# TMS320F28335_DSP.net
KiCad netlist of a schematic drawn in Altium Designer
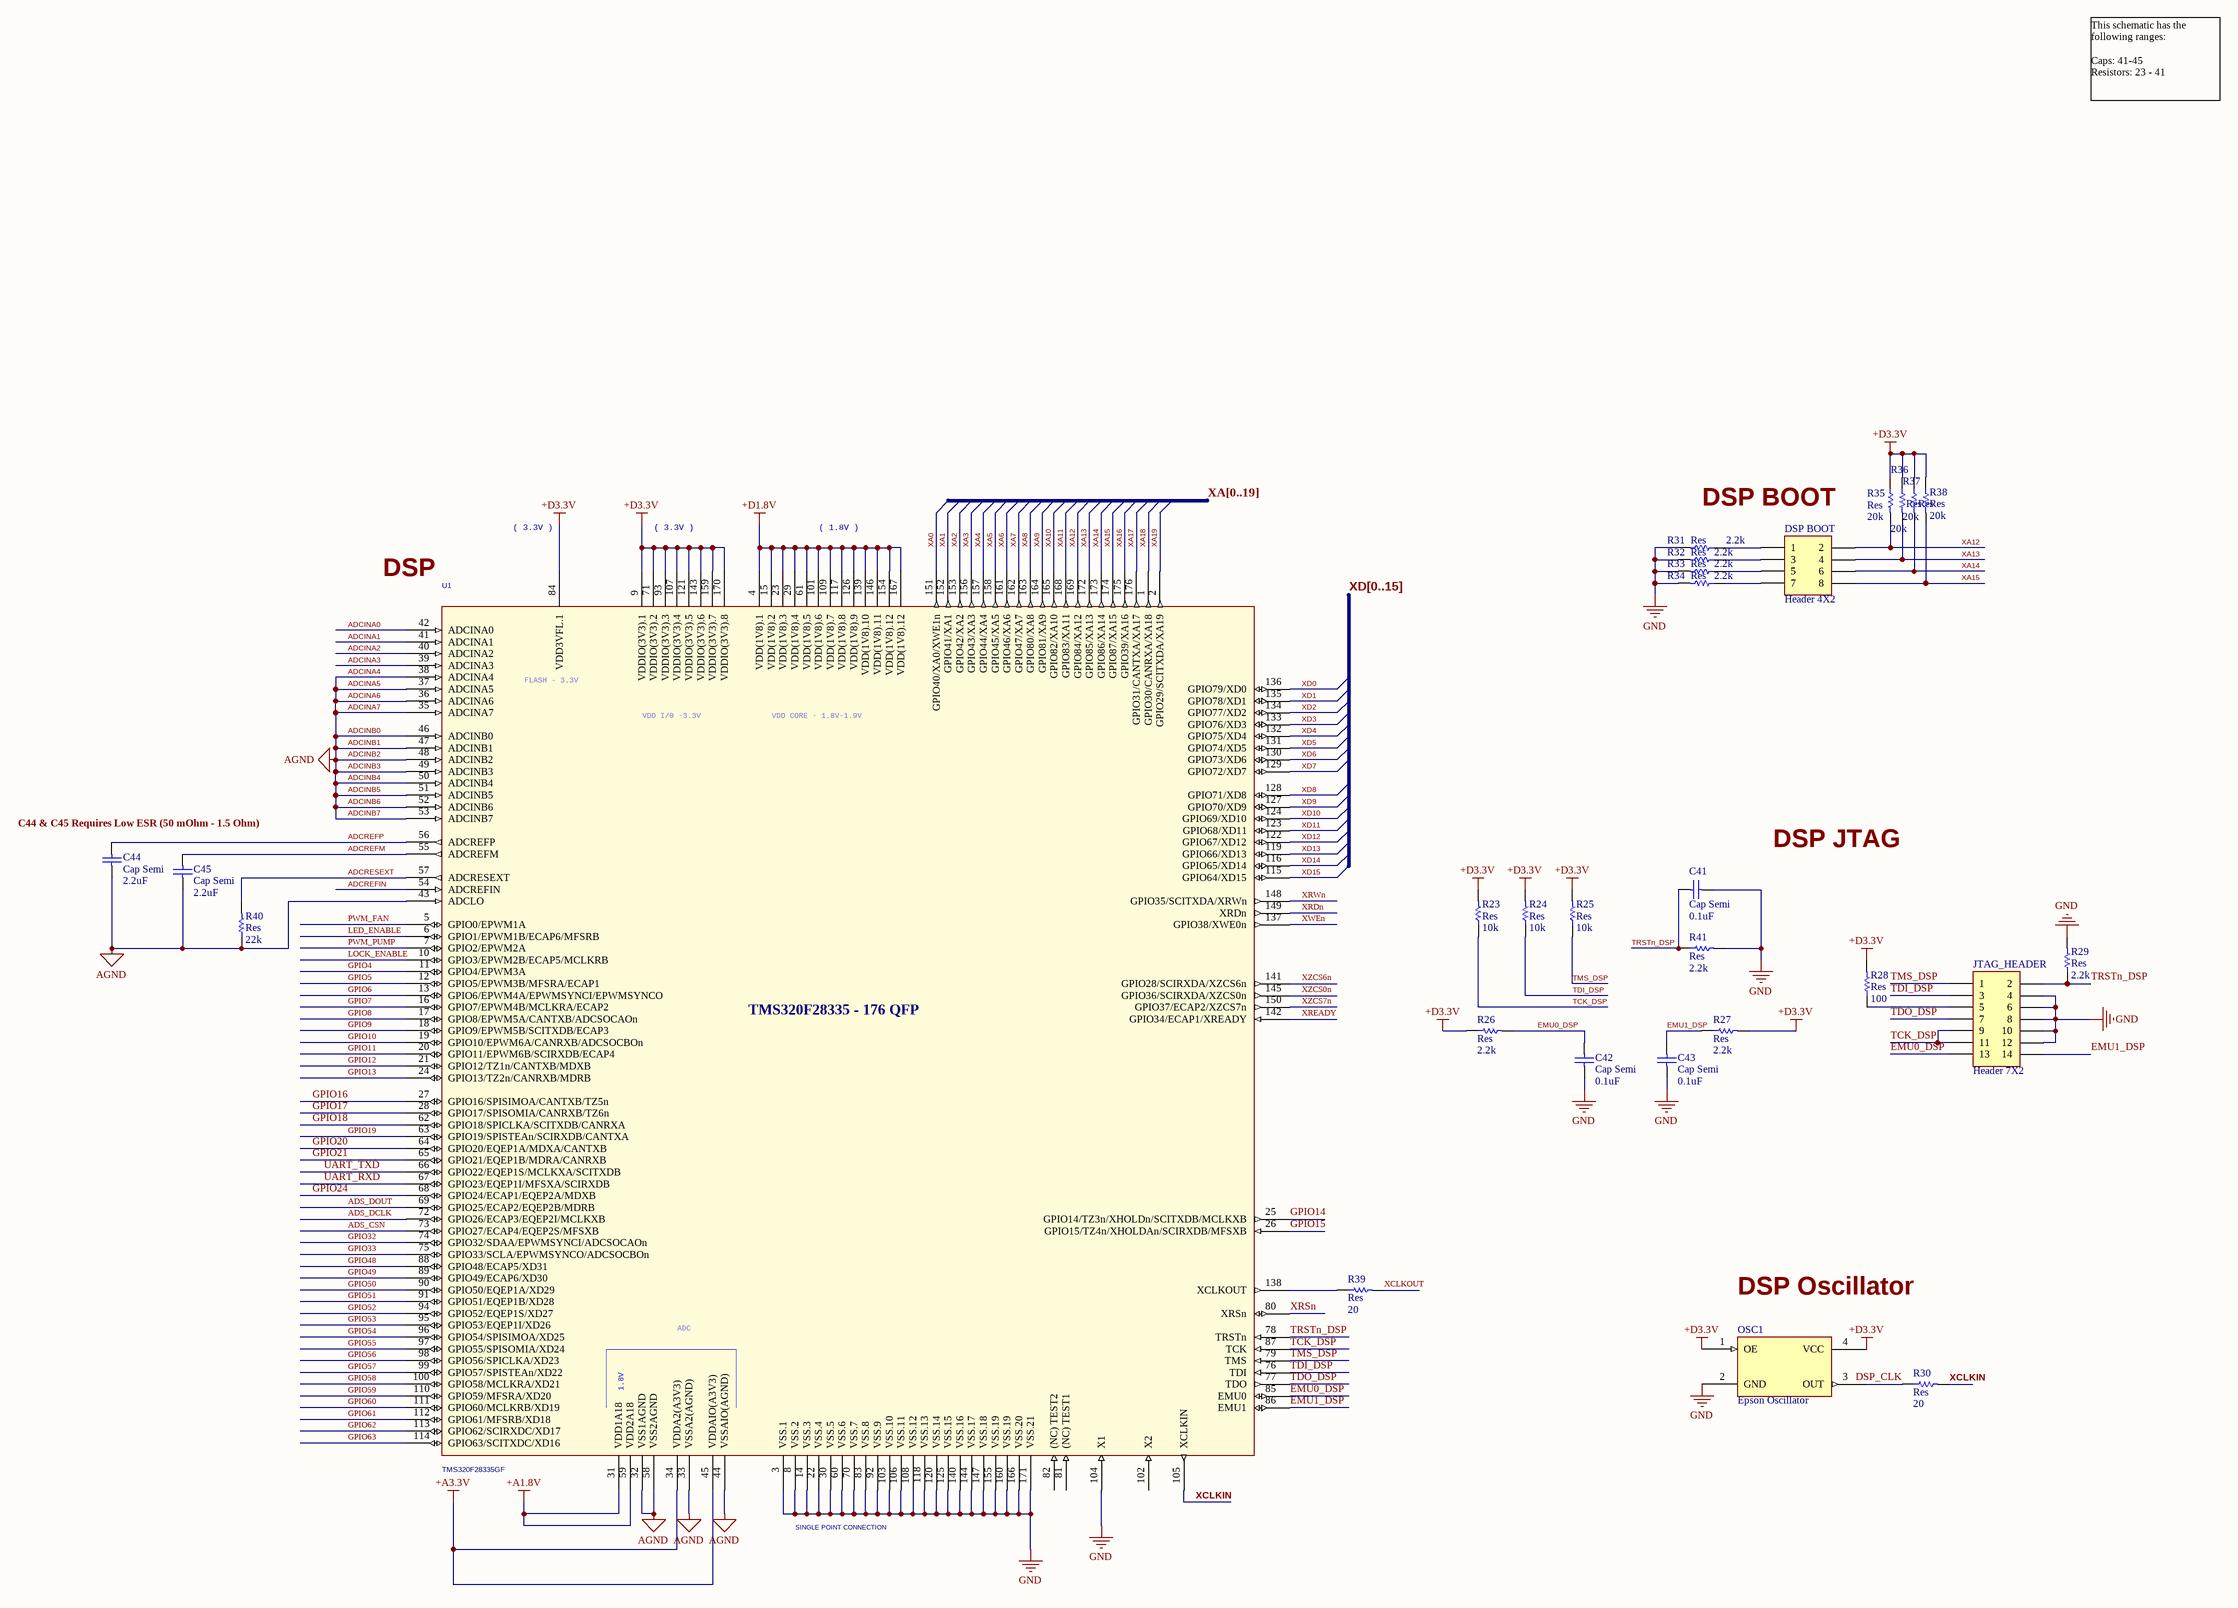
[diagram p0: TMS320F28335_DSP.SchDoc]

(export (version "E")
  (design (tool "Eeschema 10.0.6"))
  (components
    (comp (ref "C41")
      (value "Cap Semi")
      (footprint "0805")
      (description "Capacitor (Semiconductor SIM Model)")
      (fields (field (name "ALTIUM_VALUE") "0.1uF") (field (name "PUBLISHER") "Altium Limited"))
      (libsource (lib "Miscellaneous Devices") (part "Cap Semi"))
    )
    (comp (ref "C42")
      (value "Cap Semi")
      (footprint "0805")
      (description "Capacitor (Semiconductor SIM Model)")
      (fields (field (name "ALTIUM_VALUE") "0.1uF") (field (name "PUBLISHER") "Altium Limited"))
      (libsource (lib "Miscellaneous Devices") (part "Cap Semi"))
    )
    (comp (ref "C43")
      (value "Cap Semi")
      (footprint "0805")
      (description "Capacitor (Semiconductor SIM Model)")
      (fields (field (name "ALTIUM_VALUE") "0.1uF") (field (name "PUBLISHER") "Altium Limited"))
      (libsource (lib "Miscellaneous Devices") (part "Cap Semi"))
    )
    (comp (ref "C44")
      (value "Cap Semi")
      (footprint "0805")
      (description "Capacitor (Semiconductor SIM Model)")
      (fields (field (name "ALTIUM_VALUE") "2.2uF") (field (name "PUBLISHER") "Altium Limited"))
      (libsource (lib "Miscellaneous Devices") (part "Cap Semi"))
    )
    (comp (ref "C45")
      (value "Cap Semi")
      (footprint "0805")
      (description "Capacitor (Semiconductor SIM Model)")
      (fields (field (name "ALTIUM_VALUE") "2.2uF") (field (name "PUBLISHER") "Altium Limited"))
      (libsource (lib "Miscellaneous Devices") (part "Cap Semi"))
    )
    (comp (ref "DSP BOOT")
      (value "Header 4X2")
      (footprint "HDR2X4")
      (description "Header, 4-Pin, Dual row")
      (fields (field (name "PUBLISHER") "Altium Limited"))
      (libsource (lib "Miscellaneous Connectors") (part "Header 4X2"))
    )
    (comp (ref "JTAG_HEADER")
      (value "Header 7X2")
      (footprint "HDR2X7")
      (description "Header, 7-Pin, Dual row")
      (fields (field (name "PUBLISHER") "Altium Limited"))
      (libsource (lib "Miscellaneous Connectors") (part "Header 7X2"))
    )
    (comp (ref "OSC1")
      (value "Epson Oscillator")
      (footprint "Oscillator")
      (description "15Mhz Epson Clock")
      (libsource (lib "F28335_DSC_Breakout") (part "Oscillator"))
    )
    (comp (ref "R23")
      (value "Res")
      (footprint "0805")
      (description "Semiconductor Resistor")
      (fields (field (name "ALTIUM_VALUE") "10k") (field (name "PUBLISHER") "Altium Limited"))
      (libsource (lib "F28335_DSC_Breakout") (part "Res Semi"))
    )
    (comp (ref "R24")
      (value "Res")
      (footprint "0805")
      (description "Semiconductor Resistor")
      (fields (field (name "ALTIUM_VALUE") "10k") (field (name "PUBLISHER") "Altium Limited"))
      (libsource (lib "F28335_DSC_Breakout") (part "Res Semi"))
    )
    (comp (ref "R25")
      (value "Res")
      (footprint "0805")
      (description "Semiconductor Resistor")
      (fields (field (name "ALTIUM_VALUE") "10k") (field (name "PUBLISHER") "Altium Limited"))
      (libsource (lib "F28335_DSC_Breakout") (part "Res Semi"))
    )
    (comp (ref "R26")
      (value "Res")
      (footprint "0805")
      (description "Semiconductor Resistor")
      (fields (field (name "ALTIUM_VALUE") "2.2k") (field (name "PUBLISHER") "Altium Limited"))
      (libsource (lib "F28335_DSC_Breakout") (part "Res Semi"))
    )
    (comp (ref "R27")
      (value "Res")
      (footprint "0805")
      (description "Semiconductor Resistor")
      (fields (field (name "ALTIUM_VALUE") "2.2k") (field (name "PUBLISHER") "Altium Limited"))
      (libsource (lib "F28335_DSC_Breakout") (part "Res Semi"))
    )
    (comp (ref "R28")
      (value "Res")
      (footprint "0805")
      (description "Semiconductor Resistor")
      (fields (field (name "ALTIUM_VALUE") "100") (field (name "PUBLISHER") "Altium Limited"))
      (libsource (lib "F28335_DSC_Breakout") (part "Res Semi"))
    )
    (comp (ref "R29")
      (value "Res")
      (footprint "0805")
      (description "Semiconductor Resistor")
      (fields (field (name "ALTIUM_VALUE") "2.2k") (field (name "PUBLISHER") "Altium Limited"))
      (libsource (lib "F28335_DSC_Breakout") (part "Res Semi"))
    )
    (comp (ref "R30")
      (value "Res")
      (footprint "0805")
      (description "Semiconductor Resistor")
      (fields (field (name "ALTIUM_VALUE") "20") (field (name "PUBLISHER") "Altium Limited"))
      (libsource (lib "F28335_DSC_Breakout") (part "Res Semi"))
    )
    (comp (ref "R31")
      (value "Res")
      (footprint "0805")
      (description "Semiconductor Resistor")
      (fields (field (name "ALTIUM_VALUE") "2.2k") (field (name "PUBLISHER") "Altium Limited"))
      (libsource (lib "F28335_DSC_Breakout") (part "Res Semi"))
    )
    (comp (ref "R32")
      (value "Res")
      (footprint "0805")
      (description "Semiconductor Resistor")
      (fields (field (name "ALTIUM_VALUE") "2.2k") (field (name "PUBLISHER") "Altium Limited"))
      (libsource (lib "F28335_DSC_Breakout") (part "Res Semi"))
    )
    (comp (ref "R33")
      (value "Res")
      (footprint "0805")
      (description "Semiconductor Resistor")
      (fields (field (name "ALTIUM_VALUE") "2.2k") (field (name "PUBLISHER") "Altium Limited"))
      (libsource (lib "F28335_DSC_Breakout") (part "Res Semi"))
    )
    (comp (ref "R34")
      (value "Res")
      (footprint "0805")
      (description "Semiconductor Resistor")
      (fields (field (name "ALTIUM_VALUE") "2.2k") (field (name "PUBLISHER") "Altium Limited"))
      (libsource (lib "F28335_DSC_Breakout") (part "Res Semi"))
    )
    (comp (ref "R35")
      (value "Res")
      (footprint "0805")
      (description "Semiconductor Resistor")
      (fields (field (name "ALTIUM_VALUE") "20k") (field (name "PUBLISHER") "Altium Limited"))
      (libsource (lib "F28335_DSC_Breakout") (part "Res Semi"))
    )
    (comp (ref "R36")
      (value "Res")
      (footprint "0805")
      (description "Semiconductor Resistor")
      (fields (field (name "ALTIUM_VALUE") "20k") (field (name "PUBLISHER") "Altium Limited"))
      (libsource (lib "F28335_DSC_Breakout") (part "Res Semi"))
    )
    (comp (ref "R37")
      (value "Res")
      (footprint "0805")
      (description "Semiconductor Resistor")
      (fields (field (name "ALTIUM_VALUE") "20k") (field (name "PUBLISHER") "Altium Limited"))
      (libsource (lib "F28335_DSC_Breakout") (part "Res Semi"))
    )
    (comp (ref "R38")
      (value "Res")
      (footprint "0805")
      (description "Semiconductor Resistor")
      (fields (field (name "ALTIUM_VALUE") "20k") (field (name "PUBLISHER") "Altium Limited"))
      (libsource (lib "F28335_DSC_Breakout") (part "Res Semi"))
    )
    (comp (ref "R39")
      (value "Res")
      (footprint "0805")
      (description "Semiconductor Resistor")
      (fields (field (name "ALTIUM_VALUE") "20") (field (name "PUBLISHER") "Altium Limited"))
      (libsource (lib "F28335_DSC_Breakout") (part "Res Semi"))
    )
    (comp (ref "R40")
      (value "Res")
      (footprint "0805")
      (description "Semiconductor Resistor")
      (fields (field (name "ALTIUM_VALUE") "22k") (field (name "PUBLISHER") "Altium Limited"))
      (libsource (lib "F28335_DSC_Breakout") (part "Res Semi"))
    )
    (comp (ref "R41")
      (value "Res")
      (footprint "0805")
      (description "Semiconductor Resistor")
      (fields (field (name "ALTIUM_VALUE") "2.2k") (field (name "PUBLISHER") "Altium Limited"))
      (libsource (lib "F28335_DSC_Breakout") (part "Res Semi"))
    )
    (comp (ref "U1")
      (value "TMS320F28335GF")
      (footprint "QFP176")
      (description "Texas Instruments F28335")
      (libsource (lib "addl") (part "TMS320F283XXPGF_23"))
    )
  )
  (nets
    (net (code "1") (name "+A1.8V") (class "Default")
      (node (ref "U1") (pin "31") (pinfunction "VDD1A18_31") (pintype "power_in"))
      (node (ref "U1") (pin "59") (pinfunction "VDD2A18_59") (pintype "power_in"))
    )
    (net (code "2") (name "+A3.3V") (class "Default")
      (node (ref "U1") (pin "34") (pinfunction "VDDA2(A3V3)_34") (pintype "power_in"))
      (node (ref "U1") (pin "45") (pinfunction "VDDAIO(A3V3)_45") (pintype "power_in"))
    )
    (net (code "3") (name "+D1.8V") (class "Default")
      (node (ref "U1") (pin "101") (pinfunction "VDD(1V8).6_101") (pintype "power_in"))
      (node (ref "U1") (pin "109") (pinfunction "VDD(1V8).7_109") (pintype "power_in"))
      (node (ref "U1") (pin "117") (pinfunction "VDD(1V8).8_117") (pintype "power_in"))
      (node (ref "U1") (pin "126") (pinfunction "VDD(1V8).9_126") (pintype "power_in"))
      (node (ref "U1") (pin "139") (pinfunction "VDD(1V8).10_139") (pintype "power_in"))
      (node (ref "U1") (pin "146") (pinfunction "VDD(1V8).11_146") (pintype "power_in"))
      (node (ref "U1") (pin "15") (pinfunction "VDD(1V8).2_15") (pintype "power_in"))
      (node (ref "U1") (pin "154") (pinfunction "VDD(1V8).12_154") (pintype "power_in"))
      (node (ref "U1") (pin "167") (pinfunction "VDD(1V8).12_167") (pintype "power_in"))
      (node (ref "U1") (pin "23") (pinfunction "VDD(1V8).3_23") (pintype "power_in"))
      (node (ref "U1") (pin "29") (pinfunction "VDD(1V8).4_29") (pintype "power_in"))
      (node (ref "U1") (pin "4") (pinfunction "VDD(1V8).1_4") (pintype "power_in"))
      (node (ref "U1") (pin "61") (pinfunction "VDD(1V8).5_61") (pintype "power_in"))
    )
    (net (code "4") (name "+D3.3V") (class "Default")
      (node (ref "OSC1") (pin "1") (pinfunction "OE_1") (pintype "input"))
      (node (ref "OSC1") (pin "4") (pinfunction "VCC_4") (pintype "power_in"))
      (node (ref "R23") (pin "2") (pinfunction "2_2") (pintype "passive"))
      (node (ref "R24") (pin "2") (pinfunction "2_2") (pintype "passive"))
      (node (ref "R25") (pin "2") (pinfunction "2_2") (pintype "passive"))
      (node (ref "R26") (pin "1") (pinfunction "1_1") (pintype "passive"))
      (node (ref "R27") (pin "2") (pinfunction "2_2") (pintype "passive"))
      (node (ref "R28") (pin "2") (pinfunction "2_2") (pintype "passive"))
      (node (ref "R35") (pin "1") (pinfunction "1_1") (pintype "passive"))
      (node (ref "R36") (pin "1") (pinfunction "1_1") (pintype "passive"))
      (node (ref "R37") (pin "1") (pinfunction "1_1") (pintype "passive"))
      (node (ref "R38") (pin "1") (pinfunction "1_1") (pintype "passive"))
      (node (ref "U1") (pin "107") (pinfunction "VDDIO(3V3).4_107") (pintype "power_in"))
      (node (ref "U1") (pin "121") (pinfunction "VDDIO(3V3).5_121") (pintype "power_in"))
      (node (ref "U1") (pin "143") (pinfunction "VDDIO(3V3).6_143") (pintype "power_in"))
      (node (ref "U1") (pin "159") (pinfunction "VDDIO(3V3).7_159") (pintype "power_in"))
      (node (ref "U1") (pin "170") (pinfunction "VDDIO(3V3).8_170") (pintype "power_in"))
      (node (ref "U1") (pin "71") (pinfunction "VDDIO(3V3).2_71") (pintype "power_in"))
      (node (ref "U1") (pin "84") (pinfunction "VDD3VFL.1_84") (pintype "power_in"))
      (node (ref "U1") (pin "9") (pinfunction "VDDIO(3V3).1_9") (pintype "power_in"))
      (node (ref "U1") (pin "93") (pinfunction "VDDIO(3V3).3_93") (pintype "power_in"))
    )
    (net (code "5") (name "/ADCINA0") (class "Default")
      (node (ref "U1") (pin "42") (pinfunction "ADCINA0_42") (pintype "input"))
    )
    (net (code "6") (name "/ADCINA1") (class "Default")
      (node (ref "U1") (pin "41") (pinfunction "ADCINA1_41") (pintype "input"))
    )
    (net (code "7") (name "/ADCINA2") (class "Default")
      (node (ref "U1") (pin "40") (pinfunction "ADCINA2_40") (pintype "input"))
    )
    (net (code "8") (name "/ADCINA3") (class "Default")
      (node (ref "U1") (pin "39") (pinfunction "ADCINA3_39") (pintype "input"))
    )
    (net (code "9") (name "/ADCREFIN") (class "Default")
      (node (ref "U1") (pin "54") (pinfunction "ADCREFIN_54") (pintype "input"))
    )
    (net (code "10") (name "/ADCREFM") (class "Default")
      (node (ref "C45") (pin "1") (pinfunction "1_1") (pintype "passive"))
      (node (ref "U1") (pin "55") (pinfunction "ADCREFM_55") (pintype "output"))
    )
    (net (code "11") (name "/ADCREFP") (class "Default")
      (node (ref "C44") (pin "1") (pinfunction "1_1") (pintype "passive"))
      (node (ref "U1") (pin "56") (pinfunction "ADCREFP_56") (pintype "output"))
    )
    (net (code "12") (name "/ADCRESEXT") (class "Default")
      (node (ref "R40") (pin "2") (pinfunction "2_2") (pintype "passive"))
      (node (ref "U1") (pin "57") (pinfunction "ADCRESEXT_57") (pintype "output"))
    )
    (net (code "13") (name "/ADS_CSN") (class "Default")
      (node (ref "U1") (pin "73") (pinfunction "GPIO27/ECAP4/EQEP2S/MFSXB_73") (pintype "bidirectional"))
    )
    (net (code "14") (name "/ADS_DCLK") (class "Default")
      (node (ref "U1") (pin "72") (pinfunction "GPIO26/ECAP3/EQEP2I/MCLKXB_72") (pintype "bidirectional"))
    )
    (net (code "15") (name "/ADS_DOUT") (class "Default")
      (node (ref "U1") (pin "69") (pinfunction "GPIO25/ECAP2/EQEP2B/MDRB_69") (pintype "bidirectional"))
    )
    (net (code "17") (name "/EMU0_DSP") (class "Default")
      (node (ref "C42") (pin "2") (pinfunction "2_2") (pintype "passive"))
      (node (ref "JTAG_HEADER") (pin "13") (pinfunction "13_13") (pintype "passive"))
      (node (ref "R26") (pin "2") (pinfunction "2_2") (pintype "passive"))
      (node (ref "U1") (pin "85") (pinfunction "EMU0_85") (pintype "bidirectional"))
    )
    (net (code "18") (name "/EMU1_DSP") (class "Default")
      (node (ref "C43") (pin "2") (pinfunction "2_2") (pintype "passive"))
      (node (ref "JTAG_HEADER") (pin "14") (pinfunction "14_14") (pintype "passive"))
      (node (ref "R27") (pin "1") (pinfunction "1_1") (pintype "passive"))
      (node (ref "U1") (pin "86") (pinfunction "EMU1_86") (pintype "bidirectional"))
    )
    (net (code "19") (name "/GPIO4") (class "Default")
      (node (ref "U1") (pin "11") (pinfunction "GPIO4/EPWM3A_11") (pintype "bidirectional"))
    )
    (net (code "20") (name "/GPIO5") (class "Default")
      (node (ref "U1") (pin "12") (pinfunction "GPIO5/EPWM3B/MFSRA/ECAP1_12") (pintype "bidirectional"))
    )
    (net (code "21") (name "/GPIO6") (class "Default")
      (node (ref "U1") (pin "13") (pinfunction "GPIO6/EPWM4A/EPWMSYNCI/EPWMSYNCO_13") (pintype "bidirectional"))
    )
    (net (code "22") (name "/GPIO7") (class "Default")
      (node (ref "U1") (pin "16") (pinfunction "GPIO7/EPWM4B/MCLKRA/ECAP2_16") (pintype "bidirectional"))
    )
    (net (code "23") (name "/GPIO8") (class "Default")
      (node (ref "U1") (pin "17") (pinfunction "GPIO8/EPWM5A/CANTXB/ADCSOCAOn_17") (pintype "bidirectional"))
    )
    (net (code "24") (name "/GPIO9") (class "Default")
      (node (ref "U1") (pin "18") (pinfunction "GPIO9/EPWM5B/SCITXDB/ECAP3_18") (pintype "bidirectional"))
    )
    (net (code "25") (name "/GPIO10") (class "Default")
      (node (ref "U1") (pin "19") (pinfunction "GPIO10/EPWM6A/CANRXB/ADCSOCBOn_19") (pintype "bidirectional"))
    )
    (net (code "26") (name "/GPIO11") (class "Default")
      (node (ref "U1") (pin "20") (pinfunction "GPIO11/EPWM6B/SCIRXDB/ECAP4_20") (pintype "bidirectional"))
    )
    (net (code "27") (name "/GPIO12") (class "Default")
      (node (ref "U1") (pin "21") (pinfunction "GPIO12/TZ1n/CANTXB/MDXB_21") (pintype "bidirectional"))
    )
    (net (code "28") (name "/GPIO13") (class "Default")
      (node (ref "U1") (pin "24") (pinfunction "GPIO13/TZ2n/CANRXB/MDRB_24") (pintype "bidirectional"))
    )
    (net (code "29") (name "/GPIO14") (class "Default")
      (node (ref "U1") (pin "25") (pinfunction "GPIO14/TZ3n/XHOLDn/SCITXDB/MCLKXB_25") (pintype "output"))
    )
    (net (code "30") (name "/GPIO15") (class "Default")
      (node (ref "U1") (pin "26") (pinfunction "GPIO15/TZ4n/XHOLDAn/SCIRXDB/MFSXB_26") (pintype "input"))
    )
    (net (code "31") (name "/GPIO16") (class "Default")
      (node (ref "U1") (pin "27") (pinfunction "GPIO16/SPISIMOA/CANTXB/TZ5n_27") (pintype "bidirectional"))
    )
    (net (code "32") (name "/GPIO17") (class "Default")
      (node (ref "U1") (pin "28") (pinfunction "GPIO17/SPISOMIA/CANRXB/TZ6n_28") (pintype "bidirectional"))
    )
    (net (code "33") (name "/GPIO18") (class "Default")
      (node (ref "U1") (pin "62") (pinfunction "GPIO18/SPICLKA/SCITXDB/CANRXA_62") (pintype "bidirectional"))
    )
    (net (code "34") (name "/GPIO19") (class "Default")
      (node (ref "U1") (pin "63") (pinfunction "GPIO19/SPISTEAn/SCIRXDB/CANTXA_63") (pintype "bidirectional"))
    )
    (net (code "35") (name "/GPIO20") (class "Default")
      (node (ref "U1") (pin "64") (pinfunction "GPIO20/EQEP1A/MDXA/CANTXB_64") (pintype "bidirectional"))
    )
    (net (code "36") (name "/GPIO21") (class "Default")
      (node (ref "U1") (pin "65") (pinfunction "GPIO21/EQEP1B/MDRA/CANRXB_65") (pintype "bidirectional"))
    )
    (net (code "37") (name "/GPIO24") (class "Default")
      (node (ref "U1") (pin "68") (pinfunction "GPIO24/ECAP1/EQEP2A/MDXB_68") (pintype "bidirectional"))
    )
    (net (code "38") (name "/GPIO32") (class "Default")
      (node (ref "U1") (pin "74") (pinfunction "GPIO32/SDAA/EPWMSYNCI/ADCSOCAOn_74") (pintype "bidirectional"))
    )
    (net (code "39") (name "/GPIO33") (class "Default")
      (node (ref "U1") (pin "75") (pinfunction "GPIO33/SCLA/EPWMSYNCO/ADCSOCBOn_75") (pintype "bidirectional"))
    )
    (net (code "40") (name "/GPIO48") (class "Default")
      (node (ref "U1") (pin "88") (pinfunction "GPIO48/ECAP5/XD31_88") (pintype "bidirectional"))
    )
    (net (code "41") (name "/GPIO49") (class "Default")
      (node (ref "U1") (pin "89") (pinfunction "GPIO49/ECAP6/XD30_89") (pintype "bidirectional"))
    )
    (net (code "42") (name "/GPIO50") (class "Default")
      (node (ref "U1") (pin "90") (pinfunction "GPIO50/EQEP1A/XD29_90") (pintype "bidirectional"))
    )
    (net (code "43") (name "/GPIO51") (class "Default")
      (node (ref "U1") (pin "91") (pinfunction "GPIO51/EQEP1B/XD28_91") (pintype "bidirectional"))
    )
    (net (code "44") (name "/GPIO52") (class "Default")
      (node (ref "U1") (pin "94") (pinfunction "GPIO52/EQEP1S/XD27_94") (pintype "bidirectional"))
    )
    (net (code "45") (name "/GPIO53") (class "Default")
      (node (ref "U1") (pin "95") (pinfunction "GPIO53/EQEP1I/XD26_95") (pintype "bidirectional"))
    )
    (net (code "46") (name "/GPIO54") (class "Default")
      (node (ref "U1") (pin "96") (pinfunction "GPIO54/SPISIMOA/XD25_96") (pintype "bidirectional"))
    )
    (net (code "47") (name "/GPIO55") (class "Default")
      (node (ref "U1") (pin "97") (pinfunction "GPIO55/SPISOMIA/XD24_97") (pintype "bidirectional"))
    )
    (net (code "48") (name "/GPIO56") (class "Default")
      (node (ref "U1") (pin "98") (pinfunction "GPIO56/SPICLKA/XD23_98") (pintype "bidirectional"))
    )
    (net (code "49") (name "/GPIO57") (class "Default")
      (node (ref "U1") (pin "99") (pinfunction "GPIO57/SPISTEAn/XD22_99") (pintype "bidirectional"))
    )
    (net (code "50") (name "/GPIO58") (class "Default")
      (node (ref "U1") (pin "100") (pinfunction "GPIO58/MCLKRA/XD21_100") (pintype "bidirectional"))
    )
    (net (code "51") (name "/GPIO59") (class "Default")
      (node (ref "U1") (pin "110") (pinfunction "GPIO59/MFSRA/XD20_110") (pintype "bidirectional"))
    )
    (net (code "52") (name "/GPIO60") (class "Default")
      (node (ref "U1") (pin "111") (pinfunction "GPIO60/MCLKRB/XD19_111") (pintype "bidirectional"))
    )
    (net (code "53") (name "/GPIO61") (class "Default")
      (node (ref "U1") (pin "112") (pinfunction "GPIO61/MFSRB/XD18_112") (pintype "bidirectional"))
    )
    (net (code "54") (name "/GPIO62") (class "Default")
      (node (ref "U1") (pin "113") (pinfunction "GPIO62/SCIRXDC/XD17_113") (pintype "bidirectional"))
    )
    (net (code "55") (name "/GPIO63") (class "Default")
      (node (ref "U1") (pin "114") (pinfunction "GPIO63/SCITXDC/XD16_114") (pintype "bidirectional"))
    )
    (net (code "56") (name "/LED_ENABLE") (class "Default")
      (node (ref "U1") (pin "6") (pinfunction "GPIO1/EPWM1B/ECAP6/MFSRB_6") (pintype "bidirectional"))
    )
    (net (code "57") (name "/LOCK_ENABLE") (class "Default")
      (node (ref "U1") (pin "10") (pinfunction "GPIO3/EPWM2B/ECAP5/MCLKRB_10") (pintype "bidirectional"))
    )
    (net (code "58") (name "/PWM_FAN") (class "Default")
      (node (ref "U1") (pin "5") (pinfunction "GPIO0/EPWM1A_5") (pintype "bidirectional"))
    )
    (net (code "59") (name "/PWM_PUMP") (class "Default")
      (node (ref "U1") (pin "7") (pinfunction "GPIO2/EPWM2A_7") (pintype "bidirectional"))
    )
    (net (code "60") (name "/TCK_DSP") (class "Default")
      (node (ref "JTAG_HEADER") (pin "11") (pinfunction "11_11") (pintype "passive"))
      (node (ref "JTAG_HEADER") (pin "9") (pinfunction "9_9") (pintype "passive"))
      (node (ref "R23") (pin "1") (pinfunction "1_1") (pintype "passive"))
      (node (ref "U1") (pin "87") (pinfunction "TCK_87") (pintype "input"))
    )
    (net (code "61") (name "/TDI_DSP") (class "Default")
      (node (ref "JTAG_HEADER") (pin "3") (pinfunction "3_3") (pintype "passive"))
      (node (ref "R24") (pin "1") (pinfunction "1_1") (pintype "passive"))
      (node (ref "U1") (pin "76") (pinfunction "TDI_76") (pintype "input"))
    )
    (net (code "62") (name "/TDO_DSP") (class "Default")
      (node (ref "JTAG_HEADER") (pin "7") (pinfunction "7_7") (pintype "passive"))
      (node (ref "U1") (pin "77") (pinfunction "TDO_77") (pintype "output"))
    )
    (net (code "63") (name "/TMS_DSP") (class "Default")
      (node (ref "JTAG_HEADER") (pin "1") (pinfunction "1_1") (pintype "passive"))
      (node (ref "R25") (pin "1") (pinfunction "1_1") (pintype "passive"))
      (node (ref "U1") (pin "79") (pinfunction "TMS_79") (pintype "input"))
    )
    (net (code "64") (name "/TRSTn_DSP") (class "Default")
      (node (ref "C41") (pin "2") (pinfunction "2_2") (pintype "passive"))
      (node (ref "JTAG_HEADER") (pin "2") (pinfunction "2_2") (pintype "passive"))
      (node (ref "R29") (pin "1") (pinfunction "1_1") (pintype "passive"))
      (node (ref "R41") (pin "1") (pinfunction "1_1") (pintype "passive"))
      (node (ref "U1") (pin "78") (pinfunction "TRSTn_78") (pintype "input"))
    )
    (net (code "65") (name "/UART_RXD") (class "Default")
      (node (ref "U1") (pin "67") (pinfunction "GPIO23/EQEP1I/MFSXA/SCIRXDB_67") (pintype "bidirectional"))
    )
    (net (code "66") (name "/UART_TXD") (class "Default")
      (node (ref "U1") (pin "66") (pinfunction "GPIO22/EQEP1S/MCLKXA/SCITXDB_66") (pintype "bidirectional"))
    )
    (net (code "67") (name "/XA0") (class "Default")
      (node (ref "U1") (pin "151") (pinfunction "GPIO40/XA0/XWE1n_151") (pintype "output"))
    )
    (net (code "68") (name "/XA1") (class "Default")
      (node (ref "U1") (pin "152") (pinfunction "GPIO41/XA1_152") (pintype "output"))
    )
    (net (code "69") (name "/XA2") (class "Default")
      (node (ref "U1") (pin "153") (pinfunction "GPIO42/XA2_153") (pintype "output"))
    )
    (net (code "70") (name "/XA3") (class "Default")
      (node (ref "U1") (pin "156") (pinfunction "GPIO43/XA3_156") (pintype "output"))
    )
    (net (code "71") (name "/XA4") (class "Default")
      (node (ref "U1") (pin "157") (pinfunction "GPIO44/XA4_157") (pintype "output"))
    )
    (net (code "72") (name "/XA5") (class "Default")
      (node (ref "U1") (pin "158") (pinfunction "GPIO45/XA5_158") (pintype "output"))
    )
    (net (code "73") (name "/XA6") (class "Default")
      (node (ref "U1") (pin "161") (pinfunction "GPIO46/XA6_161") (pintype "output"))
    )
    (net (code "74") (name "/XA7") (class "Default")
      (node (ref "U1") (pin "162") (pinfunction "GPIO47/XA7_162") (pintype "output"))
    )
    (net (code "75") (name "/XA8") (class "Default")
      (node (ref "U1") (pin "163") (pinfunction "GPIO80/XA8_163") (pintype "output"))
    )
    (net (code "76") (name "/XA9") (class "Default")
      (node (ref "U1") (pin "164") (pinfunction "GPIO81/XA9_164") (pintype "output"))
    )
    (net (code "77") (name "/XA10") (class "Default")
      (node (ref "U1") (pin "165") (pinfunction "GPIO82/XA10_165") (pintype "output"))
    )
    (net (code "78") (name "/XA11") (class "Default")
      (node (ref "U1") (pin "168") (pinfunction "GPIO83/XA11_168") (pintype "output"))
    )
    (net (code "79") (name "/XA12") (class "Default")
      (node (ref "DSP BOOT") (pin "2") (pinfunction "2_2") (pintype "passive"))
      (node (ref "R35") (pin "2") (pinfunction "2_2") (pintype "passive"))
      (node (ref "U1") (pin "169") (pinfunction "GPIO84/XA12_169") (pintype "output"))
    )
    (net (code "80") (name "/XA13") (class "Default")
      (node (ref "DSP BOOT") (pin "4") (pinfunction "4_4") (pintype "passive"))
      (node (ref "R36") (pin "2") (pinfunction "2_2") (pintype "passive"))
      (node (ref "U1") (pin "172") (pinfunction "GPIO85/XA13_172") (pintype "output"))
    )
    (net (code "81") (name "/XA14") (class "Default")
      (node (ref "DSP BOOT") (pin "6") (pinfunction "6_6") (pintype "passive"))
      (node (ref "R37") (pin "2") (pinfunction "2_2") (pintype "passive"))
      (node (ref "U1") (pin "173") (pinfunction "GPIO86/XA14_173") (pintype "output"))
    )
    (net (code "82") (name "/XA15") (class "Default")
      (node (ref "DSP BOOT") (pin "8") (pinfunction "8_8") (pintype "passive"))
      (node (ref "R38") (pin "2") (pinfunction "2_2") (pintype "passive"))
      (node (ref "U1") (pin "174") (pinfunction "GPIO87/XA15_174") (pintype "output"))
    )
    (net (code "83") (name "/XA16") (class "Default")
      (node (ref "U1") (pin "175") (pinfunction "GPIO39/XA16_175") (pintype "output"))
    )
    (net (code "84") (name "/XA17") (class "Default")
      (node (ref "U1") (pin "176") (pinfunction "GPIO31/CANTXA/XA17_176") (pintype "output"))
    )
    (net (code "85") (name "/XA18") (class "Default")
      (node (ref "U1") (pin "1") (pinfunction "GPIO30/CANRXA/XA18_1") (pintype "output"))
    )
    (net (code "86") (name "/XA19") (class "Default")
      (node (ref "U1") (pin "2") (pinfunction "GPIO29/SCITXDA/XA19_2") (pintype "output"))
    )
    (net (code "88") (name "/XCLKIN") (class "Default")
      (node (ref "R30") (pin "2") (pinfunction "2_2") (pintype "passive"))
      (node (ref "U1") (pin "105") (pinfunction "XCLKIN_105") (pintype "output"))
    )
    (net (code "89") (name "/XCLKOUT") (class "Default")
      (node (ref "R39") (pin "2") (pinfunction "2_2") (pintype "passive"))
    )
    (net (code "90") (name "/XD0") (class "Default")
      (node (ref "U1") (pin "136") (pinfunction "GPIO79/XD0_136") (pintype "bidirectional"))
    )
    (net (code "91") (name "/XD1") (class "Default")
      (node (ref "U1") (pin "135") (pinfunction "GPIO78/XD1_135") (pintype "bidirectional"))
    )
    (net (code "92") (name "/XD2") (class "Default")
      (node (ref "U1") (pin "134") (pinfunction "GPIO77/XD2_134") (pintype "bidirectional"))
    )
    (net (code "93") (name "/XD3") (class "Default")
      (node (ref "U1") (pin "133") (pinfunction "GPIO76/XD3_133") (pintype "bidirectional"))
    )
    (net (code "94") (name "/XD4") (class "Default")
      (node (ref "U1") (pin "132") (pinfunction "GPIO75/XD4_132") (pintype "bidirectional"))
    )
    (net (code "95") (name "/XD5") (class "Default")
      (node (ref "U1") (pin "131") (pinfunction "GPIO74/XD5_131") (pintype "bidirectional"))
    )
    (net (code "96") (name "/XD6") (class "Default")
      (node (ref "U1") (pin "130") (pinfunction "GPIO73/XD6_130") (pintype "bidirectional"))
    )
    (net (code "97") (name "/XD7") (class "Default")
      (node (ref "U1") (pin "129") (pinfunction "GPIO72/XD7_129") (pintype "bidirectional"))
    )
    (net (code "98") (name "/XD8") (class "Default")
      (node (ref "U1") (pin "128") (pinfunction "GPIO71/XD8_128") (pintype "bidirectional"))
    )
    (net (code "99") (name "/XD9") (class "Default")
      (node (ref "U1") (pin "127") (pinfunction "GPIO70/XD9_127") (pintype "bidirectional"))
    )
    (net (code "100") (name "/XD10") (class "Default")
      (node (ref "U1") (pin "124") (pinfunction "GPIO69/XD10_124") (pintype "bidirectional"))
    )
    (net (code "101") (name "/XD11") (class "Default")
      (node (ref "U1") (pin "123") (pinfunction "GPIO68/XD11_123") (pintype "bidirectional"))
    )
    (net (code "102") (name "/XD12") (class "Default")
      (node (ref "U1") (pin "122") (pinfunction "GPIO67/XD12_122") (pintype "bidirectional"))
    )
    (net (code "103") (name "/XD13") (class "Default")
      (node (ref "U1") (pin "119") (pinfunction "GPIO66/XD13_119") (pintype "bidirectional"))
    )
    (net (code "104") (name "/XD14") (class "Default")
      (node (ref "U1") (pin "116") (pinfunction "GPIO65/XD14_116") (pintype "bidirectional"))
    )
    (net (code "105") (name "/XD15") (class "Default")
      (node (ref "U1") (pin "115") (pinfunction "GPIO64/XD15_115") (pintype "bidirectional"))
    )
    (net (code "107") (name "/XRDn") (class "Default")
      (node (ref "U1") (pin "149") (pinfunction "XRDn_149") (pintype "output"))
    )
    (net (code "108") (name "/XREADY") (class "Default")
      (node (ref "U1") (pin "142") (pinfunction "GPIO34/ECAP1/XREADY_142") (pintype "input"))
    )
    (net (code "109") (name "/XRSn") (class "Default")
      (node (ref "U1") (pin "80") (pinfunction "XRSn_80") (pintype "bidirectional"))
    )
    (net (code "110") (name "/XRWn") (class "Default")
      (node (ref "U1") (pin "148") (pinfunction "GPIO35/SCITXDA/XRWn_148") (pintype "output"))
    )
    (net (code "111") (name "/XWEn") (class "Default")
      (node (ref "U1") (pin "137") (pinfunction "GPIO38/XWE0n_137") (pintype "output"))
    )
    (net (code "112") (name "/XZCS0n") (class "Default")
      (node (ref "U1") (pin "145") (pinfunction "GPIO36/SCIRXDA/XZCS0n_145") (pintype "output"))
    )
    (net (code "113") (name "/XZCS6n") (class "Default")
      (node (ref "U1") (pin "141") (pinfunction "GPIO28/SCIRXDA/XZCS6n_141") (pintype "output"))
    )
    (net (code "114") (name "/XZCS7n") (class "Default")
      (node (ref "U1") (pin "150") (pinfunction "GPIO37/ECAP2/XZCS7n_150") (pintype "output"))
    )
    (net (code "115") (name "AGND") (class "Default")
      (node (ref "C44") (pin "2") (pinfunction "2_2") (pintype "passive"))
      (node (ref "C45") (pin "2") (pinfunction "2_2") (pintype "passive"))
      (node (ref "R40") (pin "1") (pinfunction "1_1") (pintype "passive"))
      (node (ref "U1") (pin "32") (pinfunction "VSS1AGND_32") (pintype "power_in"))
      (node (ref "U1") (pin "33") (pinfunction "VSSA2(AGND)_33") (pintype "power_in"))
      (node (ref "U1") (pin "35") (pinfunction "ADCINA7_35") (pintype "input"))
      (node (ref "U1") (pin "36") (pinfunction "ADCINA6_36") (pintype "input"))
      (node (ref "U1") (pin "37") (pinfunction "ADCINA5_37") (pintype "input"))
      (node (ref "U1") (pin "38") (pinfunction "ADCINA4_38") (pintype "input"))
      (node (ref "U1") (pin "43") (pinfunction "ADCLO_43") (pintype "input"))
      (node (ref "U1") (pin "44") (pinfunction "VSSAIO(AGND)_44") (pintype "power_in"))
      (node (ref "U1") (pin "46") (pinfunction "ADCINB0_46") (pintype "input"))
      (node (ref "U1") (pin "47") (pinfunction "ADCINB1_47") (pintype "input"))
      (node (ref "U1") (pin "48") (pinfunction "ADCINB2_48") (pintype "input"))
      (node (ref "U1") (pin "49") (pinfunction "ADCINB3_49") (pintype "input"))
      (node (ref "U1") (pin "50") (pinfunction "ADCINB4_50") (pintype "input"))
      (node (ref "U1") (pin "51") (pinfunction "ADCINB5_51") (pintype "input"))
      (node (ref "U1") (pin "52") (pinfunction "ADCINB6_52") (pintype "input"))
      (node (ref "U1") (pin "53") (pinfunction "ADCINB7_53") (pintype "input"))
      (node (ref "U1") (pin "58") (pinfunction "VSS2AGND_58") (pintype "power_in"))
    )
    (net (code "116") (name "GND") (class "Default")
      (node (ref "C41") (pin "1") (pinfunction "1_1") (pintype "passive"))
      (node (ref "C42") (pin "1") (pinfunction "1_1") (pintype "passive"))
      (node (ref "C43") (pin "1") (pinfunction "1_1") (pintype "passive"))
      (node (ref "JTAG_HEADER") (pin "10") (pinfunction "10_10") (pintype "passive"))
      (node (ref "JTAG_HEADER") (pin "12") (pinfunction "12_12") (pintype "passive"))
      (node (ref "JTAG_HEADER") (pin "4") (pinfunction "4_4") (pintype "passive"))
      (node (ref "JTAG_HEADER") (pin "6") (pinfunction "6_6") (pintype "passive"))
      (node (ref "JTAG_HEADER") (pin "8") (pinfunction "8_8") (pintype "passive"))
      (node (ref "OSC1") (pin "2") (pinfunction "GND_2") (pintype "power_in"))
      (node (ref "R29") (pin "2") (pinfunction "2_2") (pintype "passive"))
      (node (ref "R31") (pin "2") (pinfunction "2_2") (pintype "passive"))
      (node (ref "R32") (pin "2") (pinfunction "2_2") (pintype "passive"))
      (node (ref "R33") (pin "2") (pinfunction "2_2") (pintype "passive"))
      (node (ref "R34") (pin "2") (pinfunction "2_2") (pintype "passive"))
      (node (ref "R41") (pin "2") (pinfunction "2_2") (pintype "passive"))
      (node (ref "U1") (pin "103") (pinfunction "VSS.10_103") (pintype "power_in"))
      (node (ref "U1") (pin "104") (pinfunction "X1_104") (pintype "input"))
      (node (ref "U1") (pin "106") (pinfunction "VSS.11_106") (pintype "power_in"))
      (node (ref "U1") (pin "108") (pinfunction "VSS.12_108") (pintype "power_in"))
      (node (ref "U1") (pin "118") (pinfunction "VSS.13_118") (pintype "power_in"))
      (node (ref "U1") (pin "120") (pinfunction "VSS.14_120") (pintype "power_in"))
      (node (ref "U1") (pin "125") (pinfunction "VSS.15_125") (pintype "power_in"))
      (node (ref "U1") (pin "14") (pinfunction "VSS.3_14") (pintype "power_in"))
      (node (ref "U1") (pin "140") (pinfunction "VSS.16_140") (pintype "power_in"))
      (node (ref "U1") (pin "144") (pinfunction "VSS.17_144") (pintype "power_in"))
      (node (ref "U1") (pin "147") (pinfunction "VSS.18_147") (pintype "power_in"))
      (node (ref "U1") (pin "155") (pinfunction "VSS.19_155") (pintype "power_in"))
      (node (ref "U1") (pin "160") (pinfunction "VSS.19_160") (pintype "power_in"))
      (node (ref "U1") (pin "166") (pinfunction "VSS.20_166") (pintype "power_in"))
      (node (ref "U1") (pin "171") (pinfunction "VSS.21_171") (pintype "power_in"))
      (node (ref "U1") (pin "22") (pinfunction "VSS.4_22") (pintype "power_in"))
      (node (ref "U1") (pin "3") (pinfunction "VSS.1_3") (pintype "power_in"))
      (node (ref "U1") (pin "30") (pinfunction "VSS.5_30") (pintype "power_in"))
      (node (ref "U1") (pin "60") (pinfunction "VSS.6_60") (pintype "power_in"))
      (node (ref "U1") (pin "70") (pinfunction "VSS.7_70") (pintype "power_in"))
      (node (ref "U1") (pin "8") (pinfunction "VSS.2_8") (pintype "power_in"))
      (node (ref "U1") (pin "83") (pinfunction "VSS.8_83") (pintype "power_in"))
      (node (ref "U1") (pin "92") (pinfunction "VSS.9_92") (pintype "power_in"))
    )
    (net (code "117") (name "Net-(DSP BOOT-Pad1)") (class "Default")
      (node (ref "DSP BOOT") (pin "1") (pinfunction "1_1") (pintype "passive"))
      (node (ref "R31") (pin "1") (pinfunction "1_1") (pintype "passive"))
    )
    (net (code "118") (name "Net-(DSP BOOT-Pad3)") (class "Default")
      (node (ref "DSP BOOT") (pin "3") (pinfunction "3_3") (pintype "passive"))
      (node (ref "R32") (pin "1") (pinfunction "1_1") (pintype "passive"))
    )
    (net (code "119") (name "Net-(DSP BOOT-Pad5)") (class "Default")
      (node (ref "DSP BOOT") (pin "5") (pinfunction "5_5") (pintype "passive"))
      (node (ref "R33") (pin "1") (pinfunction "1_1") (pintype "passive"))
    )
    (net (code "120") (name "Net-(DSP BOOT-Pad7)") (class "Default")
      (node (ref "DSP BOOT") (pin "7") (pinfunction "7_7") (pintype "passive"))
      (node (ref "R34") (pin "1") (pinfunction "1_1") (pintype "passive"))
    )
    (net (code "121") (name "Net-(JTAG_HEADER-Pad5)") (class "Default")
      (node (ref "JTAG_HEADER") (pin "5") (pinfunction "5_5") (pintype "passive"))
      (node (ref "R28") (pin "1") (pinfunction "1_1") (pintype "passive"))
    )
    (net (code "122") (name "Net-(OSC1-OUT)") (class "Default")
      (node (ref "OSC1") (pin "3") (pinfunction "OUT_3") (pintype "output"))
      (node (ref "R30") (pin "1") (pinfunction "1_1") (pintype "passive"))
    )
    (net (code "123") (name "Net-(U1-XCLKOUT)") (class "Default")
      (node (ref "R39") (pin "1") (pinfunction "1_1") (pintype "passive"))
      (node (ref "U1") (pin "138") (pinfunction "XCLKOUT_138") (pintype "output"))
    )
    (net (code "124") (name "unconnected-(U1-(NC)_TEST1-Pad81)") (class "Default")
      (node (ref "U1") (pin "81") (pinfunction "(NC)_TEST1_81") (pintype "input"))
    )
    (net (code "125") (name "unconnected-(U1-(NC)_TEST2-Pad82)") (class "Default")
      (node (ref "U1") (pin "82") (pinfunction "(NC)_TEST2_82") (pintype "input"))
    )
    (net (code "126") (name "unconnected-(U1-X2-Pad102)") (class "Default")
      (node (ref "U1") (pin "102") (pinfunction "X2_102") (pintype "input"))
    )
  )
)
